# Environmental.net
KiCad netlist of a schematic drawn in Altium Designer
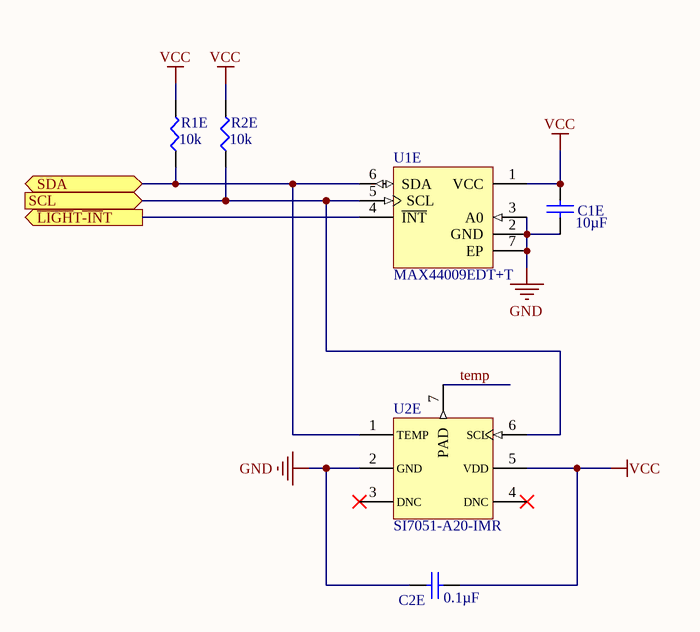
[diagram p0: Environmental.SchDoc]

(export (version "E")
  (design (tool "Eeschema 10.0.6"))
  (components
    (comp (ref "C1E")
      (value "GRT188R61C106KE13D")
      (footprint "C0603N")
      (description "10µF 16V Ceramic Capacitor X5R 0603")
      (fields
        (field (name "HOUSEPART") "NO")
        (field (name "TOLERANCE") "±10%")
        (field (name "CAPACITANCE") "10µF")
      )
      (libsource (lib "MF_Passives") (part "CAPACITOR_NP"))
    )
    (comp (ref "C2E")
      (value "GCM188R71C104KA37D")
      (footprint "C0603N")
      (fields
        (field (name "HOUSEPART") "NO")
        (field (name "TOLERANCE") "±10%")
        (field (name "VOLTAGE") "16V")
        (field (name "CAPACITANCE") "0.1µF")
      )
      (libsource (lib "MF_Passives") (part "CAPACITOR_NP"))
    )
    (comp (ref "R1E")
      (value "10k")
      (footprint "SMD-0603-RES")
      (description "RES SMD 10K OHM 1% 1/10W 0603")
      (fields
        (field (name "PART NUMBER") "ERJ-3EKF1002V")
        (field (name "DIGI-KEY PART NUMBER") "P10.0KHCT-ND")
      )
      (libsource (lib "Panasonic_ERJ_0603") (part "ERJ-3EKF1002V"))
    )
    (comp (ref "R2E")
      (value "10k")
      (footprint "SMD-0603-RES")
      (description "RES SMD 10K OHM 1% 1/10W 0603")
      (fields
        (field (name "PART NUMBER") "ERJ-3EKF1002V")
        (field (name "DIGI-KEY PART NUMBER") "P10.0KHCT-ND")
      )
      (libsource (lib "Panasonic_ERJ_0603") (part "ERJ-3EKF1002V"))
    )
    (comp (ref "U1E")
      (value "MAX44009EDT+T")
      (footprint "21-0490D")
      (description "MAX44009 light sensor")
      (libsource (lib "max44009") (part "MAX44009EDT+T"))
    )
    (comp (ref "U2E")
      (value "SI7051-A20-IMR")
      (footprint "si705x-hand")
      (description "Temperature Sensor tal, Local -40°C ~ 125°C 14 b 6-DFN (3x3)")
      (libsource (lib "SI705x") (part "CMP-6e6fa3261226b1a8-2"))
    )
  )
  (nets
    (net (code "1") (name "/SCL") (class "Default")
      (node (ref "R2E") (pin "1") (pinfunction "1_1") (pintype "passive"))
      (node (ref "U1E") (pin "5") (pinfunction "SCL_5") (pintype "input"))
      (node (ref "U2E") (pin "6") (pinfunction "SCL_6") (pintype "input"))
    )
    (net (code "2") (name "/SDA") (class "Default")
      (node (ref "R1E") (pin "1") (pinfunction "1_1") (pintype "passive"))
      (node (ref "U1E") (pin "6") (pinfunction "SDA_6") (pintype "bidirectional"))
      (node (ref "U2E") (pin "1") (pinfunction "TEMP_1") (pintype "passive"))
    )
    (net (code "3") (name "/temp") (class "Default")
      (node (ref "U2E") (pin "7") (pinfunction "PAD_7") (pintype "output"))
    )
    (net (code "4") (name "/~{LIGH}T~{-IN}T") (class "Default")
      (node (ref "U1E") (pin "4") (pinfunction "~{INT}_4") (pintype "open_collector"))
    )
    (net (code "5") (name "GND") (class "Default")
      (node (ref "C1E") (pin "1") (pinfunction "1_1") (pintype "passive"))
      (node (ref "C2E") (pin "1") (pinfunction "1_1") (pintype "passive"))
      (node (ref "U1E") (pin "2") (pinfunction "GND_2") (pintype "power_in"))
      (node (ref "U1E") (pin "3") (pinfunction "A0_3") (pintype "input"))
      (node (ref "U1E") (pin "7") (pinfunction "EP_7") (pintype "power_in"))
      (node (ref "U2E") (pin "2") (pinfunction "GND_2") (pintype "power_in"))
    )
    (net (code "6") (name "VCC") (class "Default")
      (node (ref "C1E") (pin "2") (pinfunction "2_2") (pintype "passive"))
      (node (ref "C2E") (pin "2") (pinfunction "2_2") (pintype "passive"))
      (node (ref "R1E") (pin "2") (pinfunction "2_2") (pintype "passive"))
      (node (ref "R2E") (pin "2") (pinfunction "2_2") (pintype "passive"))
      (node (ref "U1E") (pin "1") (pinfunction "VCC_1") (pintype "power_in"))
      (node (ref "U2E") (pin "5") (pinfunction "VDD_5") (pintype "power_in"))
    )
    (net (code "7") (name "unconnected-(U2E-DNC-Pad3)") (class "Default")
      (node (ref "U2E") (pin "3") (pinfunction "DNC_3") (pintype "passive+no_connect"))
    )
    (net (code "8") (name "unconnected-(U2E-DNC-Pad4)") (class "Default")
      (node (ref "U2E") (pin "4") (pinfunction "DNC_4") (pintype "passive+no_connect"))
    )
  )
)
